# IndividualTrilife_1_3.net
KiCad netlist of a schematic drawn in EAGLE
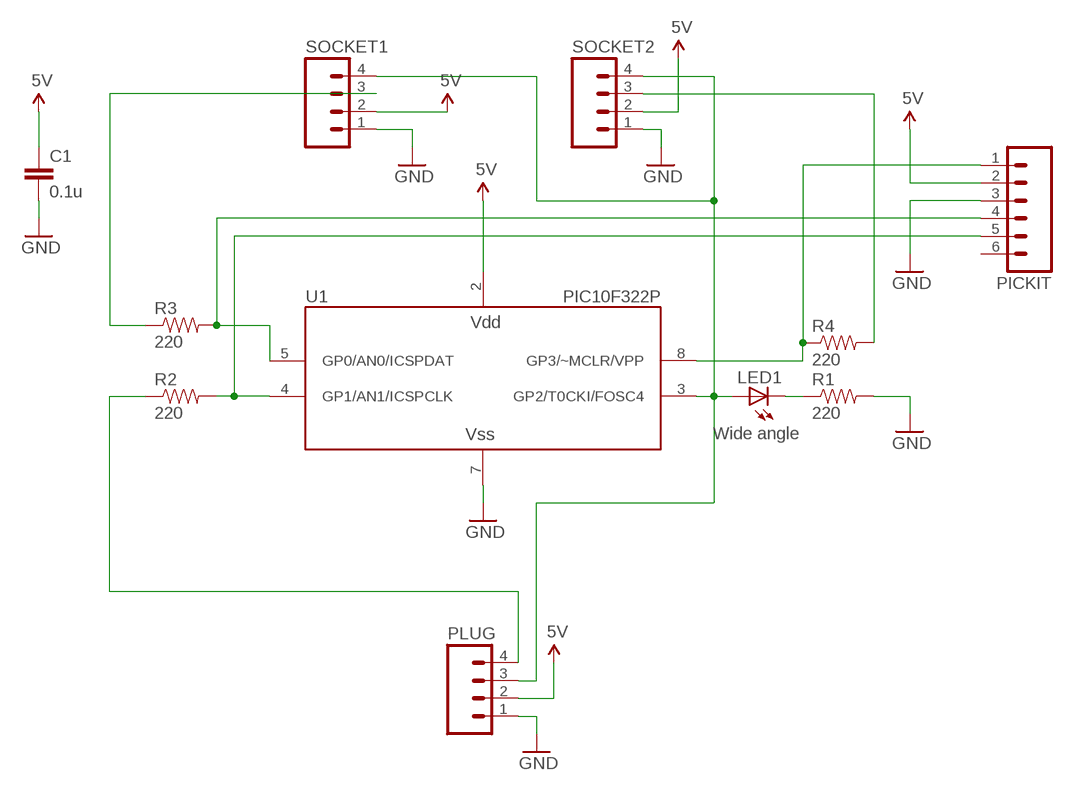
[diagram p0: schematic, sheet 1]

(export (version "E")
  (design (tool "Eeschema 10.0.6"))
  (components
    (comp (ref "C1")
      (value "0.1u")
      (footprint "eagle-import:CAP-PTH-SMALL")
      (libsource (lib "eagle-import") (part "CAPPTH"))
    )
    (comp (ref "LED1")
      (value "Wide angle")
      (footprint "eagle-import:LED5MM")
      (libsource (lib "eagle-import") (part "LED5MM"))
    )
    (comp (ref "PICKIT")
      (value "M06LOCK")
      (footprint "eagle-import:1X06_LOCK")
      (libsource (lib "eagle-import") (part "M06LOCK"))
    )
    (comp (ref "PLUG")
      (value "M04LOCK")
      (footprint "eagle-import:1X04_LOCK")
      (libsource (lib "eagle-import") (part "M04LOCK"))
    )
    (comp (ref "R1")
      (value "220")
      (footprint "eagle-import:AXIAL-0.4")
      (libsource (lib "eagle-import") (part "RESISTORPTH-1/4W"))
    )
    (comp (ref "R2")
      (value "220")
      (footprint "eagle-import:AXIAL-0.4")
      (libsource (lib "eagle-import") (part "RESISTORPTH-1/4W"))
    )
    (comp (ref "R3")
      (value "220")
      (footprint "eagle-import:AXIAL-0.4")
      (libsource (lib "eagle-import") (part "RESISTORPTH-1/4W"))
    )
    (comp (ref "R4")
      (value "220")
      (footprint "eagle-import:AXIAL-0.4")
      (libsource (lib "eagle-import") (part "RESISTORPTH-1/4W"))
    )
    (comp (ref "SOCKET1")
      (value "M04LOCK")
      (footprint "eagle-import:1X04_LOCK")
      (libsource (lib "eagle-import") (part "M04LOCK"))
    )
    (comp (ref "SOCKET2")
      (value "M04LOCK")
      (footprint "eagle-import:1X04_LOCK")
      (libsource (lib "eagle-import") (part "M04LOCK"))
    )
    (comp (ref "U1")
      (value "PIC10F322P")
      (footprint "eagle-import:DIP-8")
      (libsource (lib "eagle-import") (part "PIC10F32P2"))
    )
  )
  (nets
    (net (code "1") (name "5V") (class "Default")
      (node (ref "C1") (pin "1") (pinfunction "1_1") (pintype "passive"))
      (node (ref "PICKIT") (pin "2") (pinfunction "2_2") (pintype "passive"))
      (node (ref "PLUG") (pin "2") (pinfunction "2_2") (pintype "passive"))
      (node (ref "SOCKET1") (pin "2") (pinfunction "2_2") (pintype "passive"))
      (node (ref "SOCKET2") (pin "2") (pinfunction "2_2") (pintype "passive"))
      (node (ref "U1") (pin "2") (pinfunction "VDD_2") (pintype "power_in"))
    )
    (net (code "2") (name "GND") (class "Default")
      (node (ref "C1") (pin "2") (pinfunction "2_2") (pintype "passive"))
      (node (ref "PICKIT") (pin "3") (pinfunction "3_3") (pintype "passive"))
      (node (ref "PLUG") (pin "1") (pinfunction "1_1") (pintype "passive"))
      (node (ref "R1") (pin "P$2") (pinfunction "2_P$2") (pintype "passive"))
      (node (ref "SOCKET1") (pin "1") (pinfunction "1_1") (pintype "passive"))
      (node (ref "SOCKET2") (pin "1") (pinfunction "1_1") (pintype "passive"))
      (node (ref "U1") (pin "7") (pinfunction "VSS_7") (pintype "power_in"))
    )
    (net (code "3") (name "Net-(LED1-C)") (class "Default")
      (node (ref "LED1") (pin "K") (pinfunction "C_K") (pintype "passive"))
      (node (ref "R1") (pin "P$1") (pinfunction "1_P$1") (pintype "passive"))
    )
    (net (code "4") (name "Net-(R2-1)") (class "Default")
      (node (ref "PLUG") (pin "4") (pinfunction "4_4") (pintype "passive"))
      (node (ref "R2") (pin "P$1") (pinfunction "1_P$1") (pintype "passive"))
    )
    (net (code "5") (name "Net-(R2-2)") (class "Default")
      (node (ref "PICKIT") (pin "5") (pinfunction "5_5") (pintype "passive"))
      (node (ref "R2") (pin "P$2") (pinfunction "2_P$2") (pintype "passive"))
      (node (ref "U1") (pin "4") (pinfunction "GP1/AN1/ICSPCLK_4") (pintype "bidirectional"))
    )
    (net (code "6") (name "Net-(R3-1)") (class "Default")
      (node (ref "R3") (pin "P$1") (pinfunction "1_P$1") (pintype "passive"))
      (node (ref "SOCKET1") (pin "3") (pinfunction "3_3") (pintype "passive"))
    )
    (net (code "7") (name "Net-(R3-2)") (class "Default")
      (node (ref "PICKIT") (pin "4") (pinfunction "4_4") (pintype "passive"))
      (node (ref "R3") (pin "P$2") (pinfunction "2_P$2") (pintype "passive"))
      (node (ref "U1") (pin "5") (pinfunction "GP0/AN0/ICSPDAT_5") (pintype "bidirectional"))
    )
    (net (code "8") (name "Net-(R4-1)") (class "Default")
      (node (ref "PICKIT") (pin "1") (pinfunction "1_1") (pintype "passive"))
      (node (ref "R4") (pin "P$1") (pinfunction "1_P$1") (pintype "passive"))
      (node (ref "U1") (pin "8") (pinfunction "GP3/~{MCLR/VPP}_8") (pintype "input"))
    )
    (net (code "9") (name "Net-(R4-2)") (class "Default")
      (node (ref "R4") (pin "P$2") (pinfunction "2_P$2") (pintype "passive"))
      (node (ref "SOCKET2") (pin "3") (pinfunction "3_3") (pintype "passive"))
    )
    (net (code "10") (name "Net-(U1-GP2{slash}T0CKI{slash}FOSC4)") (class "Default")
      (node (ref "LED1") (pin "A") (pinfunction "A_A") (pintype "passive"))
      (node (ref "PLUG") (pin "3") (pinfunction "3_3") (pintype "passive"))
      (node (ref "SOCKET1") (pin "4") (pinfunction "4_4") (pintype "passive"))
      (node (ref "SOCKET2") (pin "4") (pinfunction "4_4") (pintype "passive"))
      (node (ref "U1") (pin "3") (pinfunction "GP2/T0CKI/FOSC4_3") (pintype "bidirectional"))
    )
    (net (code "11") (name "unconnected-(PICKIT-Pad6)") (class "Default")
      (node (ref "PICKIT") (pin "6") (pinfunction "6_6") (pintype "passive"))
    )
  )
)
